# Blue_Pill_-_Power.net
KiCad netlist of a schematic drawn in Altium Designer
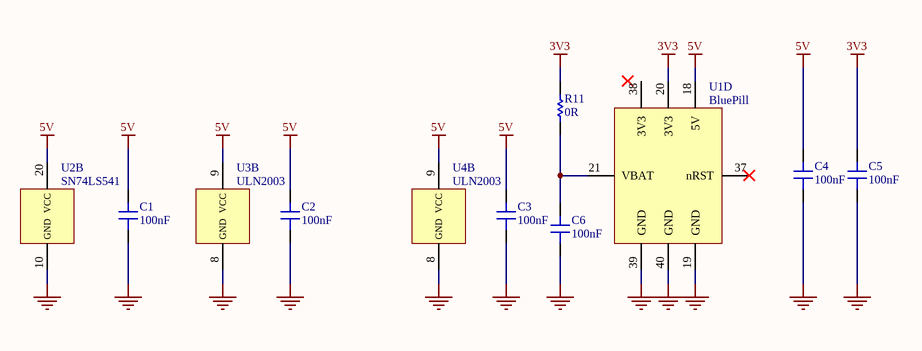
[diagram p0: Blue Pill - Power.SchDoc]

(export (version "E")
  (design (tool "Eeschema 10.0.6"))
  (components
    (comp (ref "C1")
      (value "100nF")
      (footprint "0805")
      (description "Capacitor")
      (libsource (lib "Basic") (part "Capacitor"))
    )
    (comp (ref "C2")
      (value "100nF")
      (footprint "0805")
      (description "Capacitor")
      (libsource (lib "Basic") (part "Capacitor"))
    )
    (comp (ref "C3")
      (value "100nF")
      (footprint "0805")
      (description "Capacitor")
      (libsource (lib "Basic") (part "Capacitor"))
    )
    (comp (ref "C4")
      (value "100nF")
      (footprint "0805")
      (description "Capacitor")
      (libsource (lib "Basic") (part "Capacitor"))
    )
    (comp (ref "C5")
      (value "100nF")
      (footprint "0805")
      (description "Capacitor")
      (libsource (lib "Basic") (part "Capacitor"))
    )
    (comp (ref "C6")
      (value "100nF")
      (footprint "0805")
      (description "Capacitor")
      (libsource (lib "Basic") (part "Capacitor"))
    )
    (comp (ref "R11")
      (value "0R")
      (footprint "0805")
      (description "Resistor")
      (libsource (lib "Basic") (part "Resistor"))
    )
    (comp (ref "U1")
      (value "BluePill")
      (footprint "Blue Pill")
      (description "STM32 Blue Pill")
      (libsource (lib "STM32 Blue Pill") (part "Blue Pill - Model 1"))
    )
    (comp (ref "U2")
      (value "SN74LS541")
      (footprint "PDIP20")
      (description "Octal Buffers and Line Drivers With 3-State Outputs")
      (libsource (lib "Texas Instruments") (part "SN74HC541 Type-2"))
    )
    (comp (ref "U3")
      (value "ULN2003")
      (footprint "PDIP16")
      (description "Seven Darlington arrays")
      (libsource (lib "ST Microelectronics") (part "UN200x - Model 1"))
    )
    (comp (ref "U4")
      (value "ULN2003")
      (footprint "PDIP16")
      (description "Seven Darlington arrays")
      (libsource (lib "ST Microelectronics") (part "UN200x - Model 1"))
    )
  )
  (nets
    (net (code "1") (name "3V3") (class "Default")
      (node (ref "C5") (pin "1") (pinfunction "1_1") (pintype "passive"))
      (node (ref "R11") (pin "2") (pinfunction "2_2") (pintype "passive"))
      (node (ref "U1") (pin "20") (pinfunction "3V3_20") (pintype "passive"))
    )
    (net (code "2") (name "5V") (class "Default")
      (node (ref "C1") (pin "1") (pinfunction "1_1") (pintype "passive"))
      (node (ref "C2") (pin "1") (pinfunction "1_1") (pintype "passive"))
      (node (ref "C3") (pin "1") (pinfunction "1_1") (pintype "passive"))
      (node (ref "C4") (pin "1") (pinfunction "1_1") (pintype "passive"))
      (node (ref "U1") (pin "18") (pinfunction "5V_18") (pintype "power_in"))
      (node (ref "U2") (pin "20") (pinfunction "VCC_20") (pintype "power_in"))
      (node (ref "U3") (pin "9") (pinfunction "VCC_9") (pintype "power_in"))
      (node (ref "U4") (pin "9") (pinfunction "VCC_9") (pintype "power_in"))
    )
    (net (code "3") (name "GND") (class "Default")
      (node (ref "C1") (pin "2") (pinfunction "2_2") (pintype "passive"))
      (node (ref "C2") (pin "2") (pinfunction "2_2") (pintype "passive"))
      (node (ref "C3") (pin "2") (pinfunction "2_2") (pintype "passive"))
      (node (ref "C4") (pin "2") (pinfunction "2_2") (pintype "passive"))
      (node (ref "C5") (pin "2") (pinfunction "2_2") (pintype "passive"))
      (node (ref "C6") (pin "2") (pinfunction "2_2") (pintype "passive"))
      (node (ref "U1") (pin "19") (pinfunction "GND_19") (pintype "power_in"))
      (node (ref "U1") (pin "39") (pinfunction "GND_39") (pintype "power_in"))
      (node (ref "U1") (pin "40") (pinfunction "GND_40") (pintype "power_in"))
      (node (ref "U2") (pin "10") (pinfunction "GND_10") (pintype "power_in"))
      (node (ref "U3") (pin "8") (pinfunction "GND_8") (pintype "power_in"))
      (node (ref "U4") (pin "8") (pinfunction "GND_8") (pintype "power_in"))
    )
    (net (code "4") (name "Net-(U1D-VBAT)") (class "Default")
      (node (ref "C6") (pin "1") (pinfunction "1_1") (pintype "passive"))
      (node (ref "R11") (pin "1") (pinfunction "1_1") (pintype "passive"))
      (node (ref "U1") (pin "21") (pinfunction "VBAT_21") (pintype "power_in"))
    )
    (net (code "5") (name "unconnected-(U1D-3V3-Pad38)") (class "Default")
      (node (ref "U1") (pin "38") (pinfunction "3V3_38") (pintype "power_in"))
    )
    (net (code "6") (name "unconnected-(U1D-nRST-Pad37)") (class "Default")
      (node (ref "U1") (pin "37") (pinfunction "nRST_37") (pintype "passive+no_connect"))
    )
  )
)
